# gases2.net
KiCad netlist of a schematic drawn in EAGLE
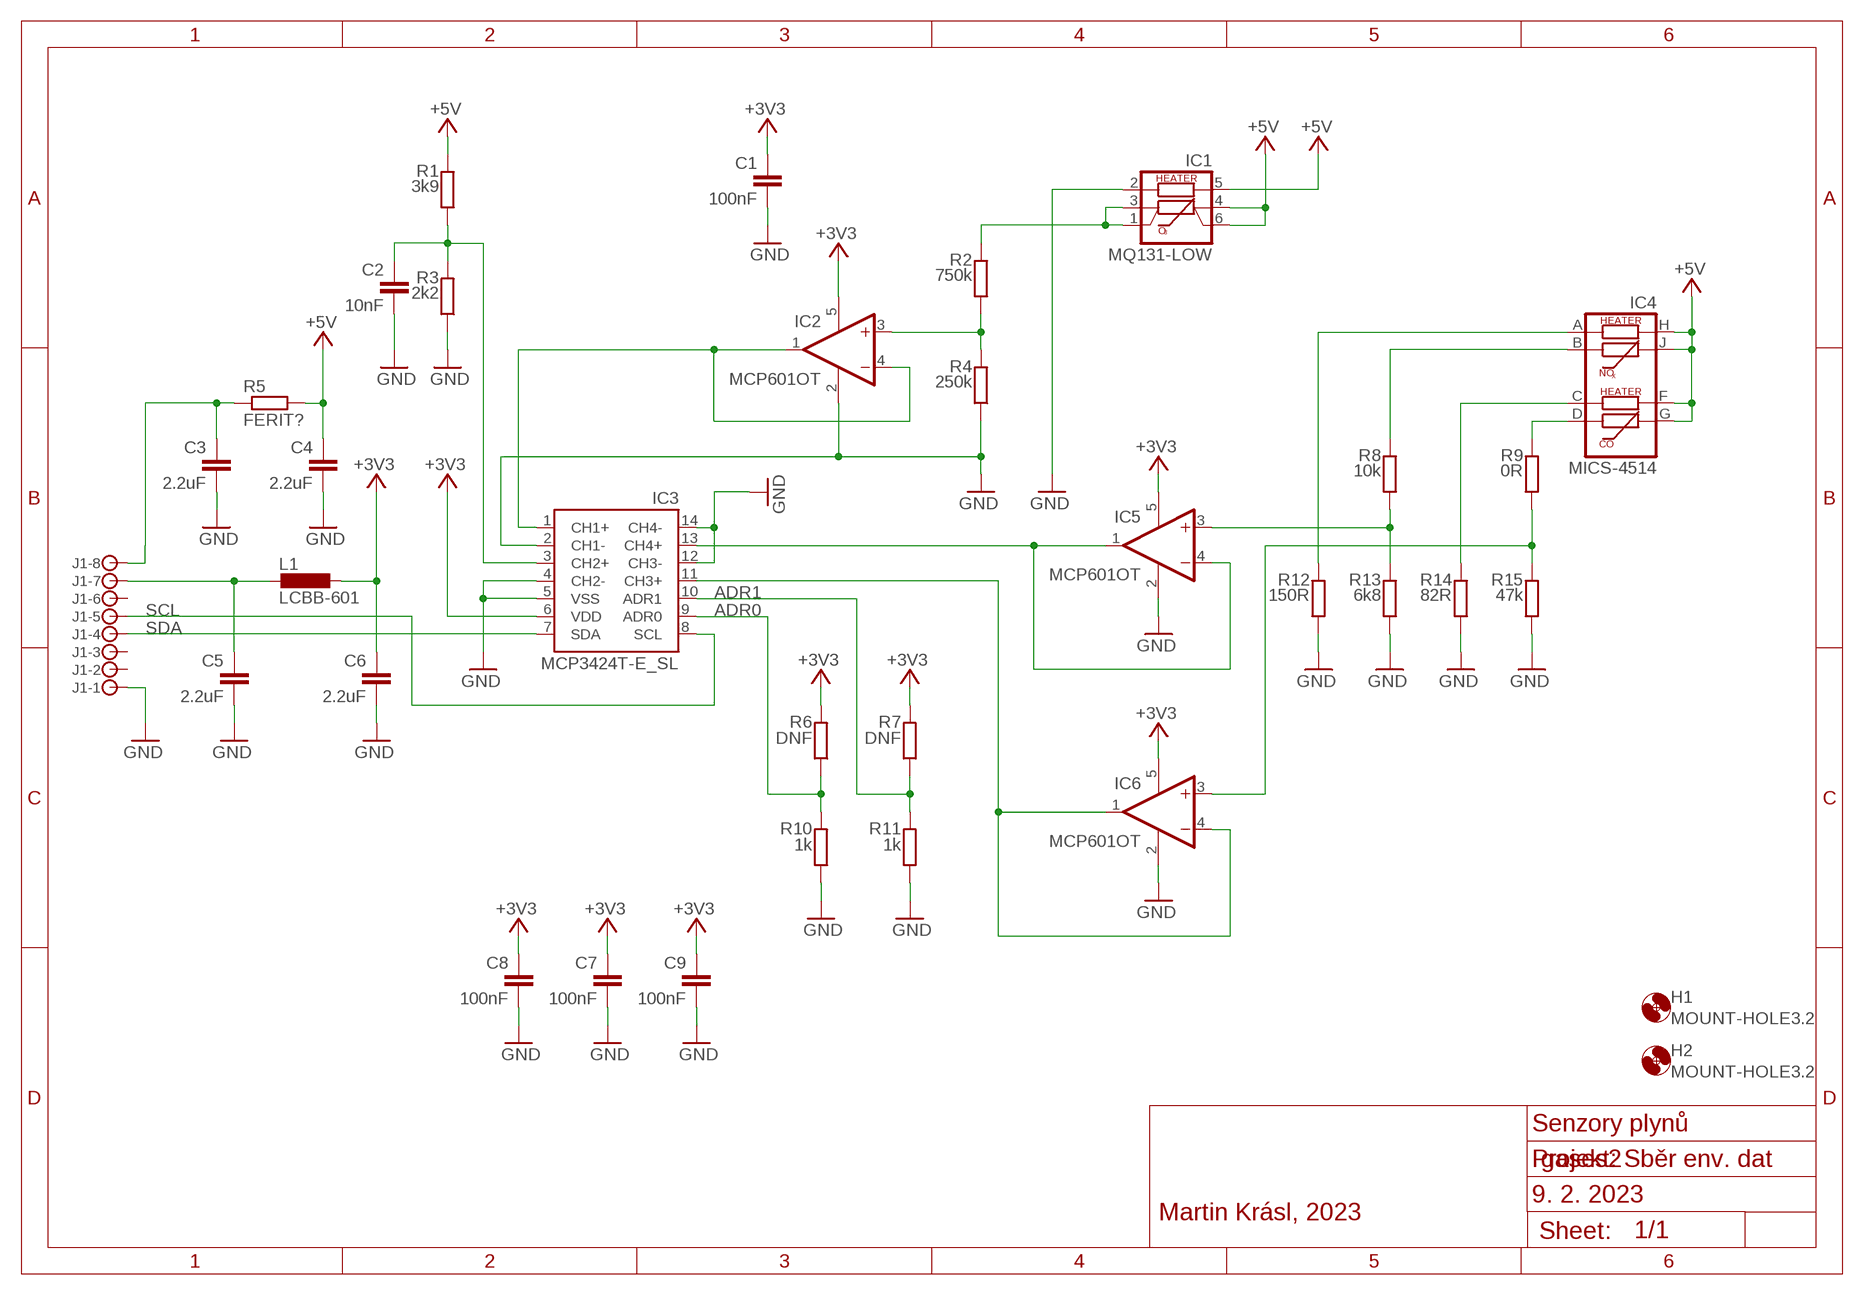
[diagram p0: schematic, sheet 1]

(export (version "E")
  (design (tool "Eeschema 10.0.6"))
  (components
    (comp (ref "C1")
      (value "100nF")
      (footprint "eagle-import:C0402")
      (libsource (lib "eagle-import") (part "C-EUC0402"))
    )
    (comp (ref "C2")
      (value "10nF")
      (footprint "eagle-import:C0402")
      (libsource (lib "eagle-import") (part "C-EUC0402"))
    )
    (comp (ref "C3")
      (value "2.2uF")
      (footprint "eagle-import:C0402")
      (libsource (lib "eagle-import") (part "C-EUC0402"))
    )
    (comp (ref "C4")
      (value "2.2uF")
      (footprint "eagle-import:C0402")
      (libsource (lib "eagle-import") (part "C-EUC0402"))
    )
    (comp (ref "C5")
      (value "2.2uF")
      (footprint "eagle-import:C0402")
      (libsource (lib "eagle-import") (part "C-EUC0402"))
    )
    (comp (ref "C6")
      (value "2.2uF")
      (footprint "eagle-import:C0402")
      (libsource (lib "eagle-import") (part "C-EUC0402"))
    )
    (comp (ref "C7")
      (value "100nF")
      (footprint "eagle-import:C0402")
      (libsource (lib "eagle-import") (part "C-EUC0402"))
    )
    (comp (ref "C8")
      (value "100nF")
      (footprint "eagle-import:C0402")
      (libsource (lib "eagle-import") (part "C-EUC0402"))
    )
    (comp (ref "C9")
      (value "100nF")
      (footprint "eagle-import:C0402")
      (libsource (lib "eagle-import") (part "C-EUC0402"))
    )
    (comp (ref "H1")
      (value "MOUNT-HOLE3.2")
      (footprint "eagle-import:3,2")
      (libsource (lib "eagle-import") (part "MOUNT-HOLE3.2"))
    )
    (comp (ref "H2")
      (value "MOUNT-HOLE3.2")
      (footprint "eagle-import:3,2")
      (libsource (lib "eagle-import") (part "MOUNT-HOLE3.2"))
    )
    (comp (ref "IC1")
      (value "MQ131-LOW")
      (footprint "eagle-import:MQ131-LOW")
      (libsource (lib "eagle-import") (part "MQ131-LOW"))
    )
    (comp (ref "IC2")
      (value "MCP601OT")
      (footprint "eagle-import:SOT23-5")
      (libsource (lib "eagle-import") (part "MCP601OT"))
    )
    (comp (ref "IC3")
      (value "MCP3424T-E_SL")
      (footprint "eagle-import:SOIC127P600X175-14N")
      (fields
        (field (name "ARROW_PART_NUMBER") "MCP3424T-E/SL")
        (field (name "MOUSER_PART_NUMBER") "579-MCP3424T-E/SL")
      )
      (libsource (lib "eagle-import") (part "MCP3424T-E_SL"))
    )
    (comp (ref "IC4")
      (value "MICS-4514")
      (footprint "eagle-import:MICS-4514")
      (libsource (lib "eagle-import") (part "MICS-4514"))
    )
    (comp (ref "IC5")
      (value "MCP601OT")
      (footprint "eagle-import:SOT23-5")
      (libsource (lib "eagle-import") (part "MCP601OT"))
    )
    (comp (ref "IC6")
      (value "MCP601OT")
      (footprint "eagle-import:SOT23-5")
      (libsource (lib "eagle-import") (part "MCP601OT"))
    )
    (comp (ref "J1")
      (value "JST-XH-8")
      (footprint "eagle-import:B8B-XH-A")
      (fields (field (name "MF") "JST") (field (name "MPN") "B8B-XH-A"))
      (libsource (lib "eagle-import") (part "JST-XH-8"))
    )
    (comp (ref "L1")
      (value "LCBB-601")
      (footprint "eagle-import:L2012C")
      (libsource (lib "eagle-import") (part "L-EU2012(0805)"))
    )
    (comp (ref "R1")
      (value "3k9")
      (footprint "eagle-import:R0402")
      (libsource (lib "eagle-import") (part "R-EU_R0402"))
    )
    (comp (ref "R2")
      (value "750k")
      (footprint "eagle-import:R0402")
      (libsource (lib "eagle-import") (part "R-EU_R0402"))
    )
    (comp (ref "R3")
      (value "2k2")
      (footprint "eagle-import:R0402")
      (libsource (lib "eagle-import") (part "R-EU_R0402"))
    )
    (comp (ref "R4")
      (value "250k")
      (footprint "eagle-import:R0402")
      (libsource (lib "eagle-import") (part "R-EU_R0402"))
    )
    (comp (ref "R5")
      (value "FERIT?")
      (footprint "eagle-import:R0805")
      (libsource (lib "eagle-import") (part "R-EU_R0805"))
    )
    (comp (ref "R6")
      (value "DNF")
      (footprint "eagle-import:R0402")
      (libsource (lib "eagle-import") (part "R-EU_R0402"))
    )
    (comp (ref "R7")
      (value "DNF")
      (footprint "eagle-import:R0402")
      (libsource (lib "eagle-import") (part "R-EU_R0402"))
    )
    (comp (ref "R8")
      (value "10k")
      (footprint "eagle-import:R0402")
      (libsource (lib "eagle-import") (part "R-EU_R0402"))
    )
    (comp (ref "R9")
      (value "0R")
      (footprint "eagle-import:R0402")
      (libsource (lib "eagle-import") (part "R-EU_R0402"))
    )
    (comp (ref "R10")
      (value "1k")
      (footprint "eagle-import:R0402")
      (libsource (lib "eagle-import") (part "R-EU_R0402"))
    )
    (comp (ref "R11")
      (value "1k")
      (footprint "eagle-import:R0402")
      (libsource (lib "eagle-import") (part "R-EU_R0402"))
    )
    (comp (ref "R12")
      (value "150R")
      (footprint "eagle-import:R1206")
      (libsource (lib "eagle-import") (part "R-EU_R1206"))
    )
    (comp (ref "R13")
      (value "6k8")
      (footprint "eagle-import:R0402")
      (libsource (lib "eagle-import") (part "R-EU_R0402"))
    )
    (comp (ref "R14")
      (value "82R")
      (footprint "eagle-import:R1206")
      (libsource (lib "eagle-import") (part "R-EU_R1206"))
    )
    (comp (ref "R15")
      (value "47k")
      (footprint "eagle-import:R0402")
      (libsource (lib "eagle-import") (part "R-EU_R0402"))
    )
  )
  (nets
    (net (code "1") (name "+3V3") (class "Default")
      (node (ref "C1") (pin "1") (pinfunction "1_1") (pintype "passive"))
      (node (ref "C6") (pin "1") (pinfunction "1_1") (pintype "passive"))
      (node (ref "C7") (pin "1") (pinfunction "1_1") (pintype "passive"))
      (node (ref "C8") (pin "1") (pinfunction "1_1") (pintype "passive"))
      (node (ref "C9") (pin "1") (pinfunction "1_1") (pintype "passive"))
      (node (ref "IC2") (pin "5") (pinfunction "V+_5") (pintype "power_in"))
      (node (ref "IC3") (pin "6") (pinfunction "VDD_6") (pintype "bidirectional"))
      (node (ref "IC5") (pin "5") (pinfunction "V+_5") (pintype "power_in"))
      (node (ref "IC6") (pin "5") (pinfunction "V+_5") (pintype "power_in"))
      (node (ref "L1") (pin "1") (pinfunction "1_1") (pintype "passive"))
      (node (ref "R6") (pin "2") (pinfunction "2_2") (pintype "passive"))
      (node (ref "R7") (pin "2") (pinfunction "2_2") (pintype "passive"))
    )
    (net (code "2") (name "+5V") (class "Default")
      (node (ref "C4") (pin "1") (pinfunction "1_1") (pintype "passive"))
      (node (ref "IC1") (pin "4") (pinfunction "4_4") (pintype "passive"))
      (node (ref "IC1") (pin "5") (pinfunction "5_5") (pintype "passive"))
      (node (ref "IC1") (pin "6") (pinfunction "6_6") (pintype "passive"))
      (node (ref "IC4") (pin "F") (pinfunction "F_F") (pintype "passive"))
      (node (ref "IC4") (pin "G") (pinfunction "G_G") (pintype "passive"))
      (node (ref "IC4") (pin "H") (pinfunction "H_H") (pintype "passive"))
      (node (ref "IC4") (pin "J") (pinfunction "J_J") (pintype "passive"))
      (node (ref "R1") (pin "2") (pinfunction "2_2") (pintype "passive"))
      (node (ref "R5") (pin "2") (pinfunction "2_2") (pintype "passive"))
    )
    (net (code "3") (name "/ADR0") (class "Default")
      (node (ref "IC3") (pin "9") (pinfunction "ADR0_9") (pintype "bidirectional"))
      (node (ref "R10") (pin "2") (pinfunction "2_2") (pintype "passive"))
      (node (ref "R6") (pin "1") (pinfunction "1_1") (pintype "passive"))
    )
    (net (code "4") (name "/ADR1") (class "Default")
      (node (ref "IC3") (pin "10") (pinfunction "ADR1_10") (pintype "bidirectional"))
      (node (ref "R11") (pin "2") (pinfunction "2_2") (pintype "passive"))
      (node (ref "R7") (pin "1") (pinfunction "1_1") (pintype "passive"))
    )
    (net (code "5") (name "/SCL") (class "Default")
      (node (ref "IC3") (pin "8") (pinfunction "SCL_8") (pintype "bidirectional"))
      (node (ref "J1") (pin "5") (pinfunction "P_5") (pintype "bidirectional"))
    )
    (net (code "6") (name "/SDA") (class "Default")
      (node (ref "IC3") (pin "7") (pinfunction "SDA_7") (pintype "bidirectional"))
      (node (ref "J1") (pin "4") (pinfunction "P_4") (pintype "bidirectional"))
    )
    (net (code "7") (name "GND") (class "Default")
      (node (ref "C1") (pin "2") (pinfunction "2_2") (pintype "passive"))
      (node (ref "C2") (pin "2") (pinfunction "2_2") (pintype "passive"))
      (node (ref "C3") (pin "2") (pinfunction "2_2") (pintype "passive"))
      (node (ref "C4") (pin "2") (pinfunction "2_2") (pintype "passive"))
      (node (ref "C5") (pin "2") (pinfunction "2_2") (pintype "passive"))
      (node (ref "C6") (pin "2") (pinfunction "2_2") (pintype "passive"))
      (node (ref "C7") (pin "2") (pinfunction "2_2") (pintype "passive"))
      (node (ref "C8") (pin "2") (pinfunction "2_2") (pintype "passive"))
      (node (ref "C9") (pin "2") (pinfunction "2_2") (pintype "passive"))
      (node (ref "IC1") (pin "2") (pinfunction "2_2") (pintype "passive"))
      (node (ref "IC2") (pin "2") (pinfunction "V-_2") (pintype "power_in"))
      (node (ref "IC3") (pin "12") (pinfunction "CH3-_12") (pintype "bidirectional"))
      (node (ref "IC3") (pin "14") (pinfunction "CH4-_14") (pintype "bidirectional"))
      (node (ref "IC3") (pin "2") (pinfunction "CH1-_2") (pintype "bidirectional"))
      (node (ref "IC3") (pin "4") (pinfunction "CH2-_4") (pintype "bidirectional"))
      (node (ref "IC3") (pin "5") (pinfunction "VSS_5") (pintype "bidirectional"))
      (node (ref "IC5") (pin "2") (pinfunction "V-_2") (pintype "power_in"))
      (node (ref "IC6") (pin "2") (pinfunction "V-_2") (pintype "power_in"))
      (node (ref "J1") (pin "1") (pinfunction "P_1") (pintype "bidirectional"))
      (node (ref "R10") (pin "1") (pinfunction "1_1") (pintype "passive"))
      (node (ref "R11") (pin "1") (pinfunction "1_1") (pintype "passive"))
      (node (ref "R12") (pin "1") (pinfunction "1_1") (pintype "passive"))
      (node (ref "R13") (pin "1") (pinfunction "1_1") (pintype "passive"))
      (node (ref "R14") (pin "1") (pinfunction "1_1") (pintype "passive"))
      (node (ref "R15") (pin "1") (pinfunction "1_1") (pintype "passive"))
      (node (ref "R3") (pin "1") (pinfunction "1_1") (pintype "passive"))
      (node (ref "R4") (pin "1") (pinfunction "1_1") (pintype "passive"))
    )
    (net (code "8") (name "Net-(IC1-Pad1)") (class "Default")
      (node (ref "IC1") (pin "1") (pinfunction "1_1") (pintype "passive"))
      (node (ref "IC1") (pin "3") (pinfunction "3_3") (pintype "passive"))
      (node (ref "R2") (pin "2") (pinfunction "2_2") (pintype "passive"))
    )
    (net (code "9") (name "Net-(IC2-+IN)") (class "Default")
      (node (ref "IC2") (pin "3") (pinfunction "+IN_3") (pintype "input"))
      (node (ref "R2") (pin "1") (pinfunction "1_1") (pintype "passive"))
      (node (ref "R4") (pin "2") (pinfunction "2_2") (pintype "passive"))
    )
    (net (code "10") (name "Net-(IC2--IN)") (class "Default")
      (node (ref "IC2") (pin "1") (pinfunction "OUT_1") (pintype "output"))
      (node (ref "IC2") (pin "4") (pinfunction "-IN_4") (pintype "input"))
      (node (ref "IC3") (pin "1") (pinfunction "CH1+_1") (pintype "bidirectional"))
    )
    (net (code "11") (name "Net-(IC3-CH2+)") (class "Default")
      (node (ref "C2") (pin "1") (pinfunction "1_1") (pintype "passive"))
      (node (ref "IC3") (pin "3") (pinfunction "CH2+_3") (pintype "bidirectional"))
      (node (ref "R1") (pin "1") (pinfunction "1_1") (pintype "passive"))
      (node (ref "R3") (pin "2") (pinfunction "2_2") (pintype "passive"))
    )
    (net (code "12") (name "Net-(IC3-CH3+)") (class "Default")
      (node (ref "IC3") (pin "11") (pinfunction "CH3+_11") (pintype "bidirectional"))
      (node (ref "IC6") (pin "1") (pinfunction "OUT_1") (pintype "output"))
      (node (ref "IC6") (pin "4") (pinfunction "-IN_4") (pintype "input"))
    )
    (net (code "13") (name "Net-(IC3-CH4+)") (class "Default")
      (node (ref "IC3") (pin "13") (pinfunction "CH4+_13") (pintype "bidirectional"))
      (node (ref "IC5") (pin "1") (pinfunction "OUT_1") (pintype "output"))
      (node (ref "IC5") (pin "4") (pinfunction "-IN_4") (pintype "input"))
    )
    (net (code "14") (name "Net-(IC4-PadA)") (class "Default")
      (node (ref "IC4") (pin "A") (pinfunction "A_A") (pintype "passive"))
      (node (ref "R12") (pin "2") (pinfunction "2_2") (pintype "passive"))
    )
    (net (code "15") (name "Net-(IC4-PadB)") (class "Default")
      (node (ref "IC4") (pin "B") (pinfunction "B_B") (pintype "passive"))
      (node (ref "R8") (pin "2") (pinfunction "2_2") (pintype "passive"))
    )
    (net (code "16") (name "Net-(IC4-PadC)") (class "Default")
      (node (ref "IC4") (pin "C") (pinfunction "C_C") (pintype "passive"))
      (node (ref "R14") (pin "2") (pinfunction "2_2") (pintype "passive"))
    )
    (net (code "17") (name "Net-(IC4-PadD)") (class "Default")
      (node (ref "IC4") (pin "D") (pinfunction "D_D") (pintype "passive"))
      (node (ref "R9") (pin "2") (pinfunction "2_2") (pintype "passive"))
    )
    (net (code "18") (name "Net-(IC5-+IN)") (class "Default")
      (node (ref "IC5") (pin "3") (pinfunction "+IN_3") (pintype "input"))
      (node (ref "R13") (pin "2") (pinfunction "2_2") (pintype "passive"))
      (node (ref "R8") (pin "1") (pinfunction "1_1") (pintype "passive"))
    )
    (net (code "19") (name "Net-(IC6-+IN)") (class "Default")
      (node (ref "IC6") (pin "3") (pinfunction "+IN_3") (pintype "input"))
      (node (ref "R15") (pin "2") (pinfunction "2_2") (pintype "passive"))
      (node (ref "R9") (pin "1") (pinfunction "1_1") (pintype "passive"))
    )
    (net (code "20") (name "Net-(J1G-P)") (class "Default")
      (node (ref "C5") (pin "1") (pinfunction "1_1") (pintype "passive"))
      (node (ref "J1") (pin "7") (pinfunction "P_7") (pintype "bidirectional"))
      (node (ref "L1") (pin "2") (pinfunction "2_2") (pintype "passive"))
    )
    (net (code "21") (name "Net-(J1H-P)") (class "Default")
      (node (ref "C3") (pin "1") (pinfunction "1_1") (pintype "passive"))
      (node (ref "J1") (pin "8") (pinfunction "P_8") (pintype "bidirectional"))
      (node (ref "R5") (pin "1") (pinfunction "1_1") (pintype "passive"))
    )
    (net (code "22") (name "unconnected-(J1B-P-Pad2)") (class "Default")
      (node (ref "J1") (pin "2") (pinfunction "P_2") (pintype "bidirectional"))
    )
    (net (code "23") (name "unconnected-(J1C-P-Pad3)") (class "Default")
      (node (ref "J1") (pin "3") (pinfunction "P_3") (pintype "bidirectional"))
    )
    (net (code "24") (name "unconnected-(J1F-P-Pad6)") (class "Default")
      (node (ref "J1") (pin "6") (pinfunction "P_6") (pintype "bidirectional"))
    )
  )
)
